# Genny_Joypad_to_Atari_Adapter.net
KiCad netlist of a schematic drawn in EAGLE
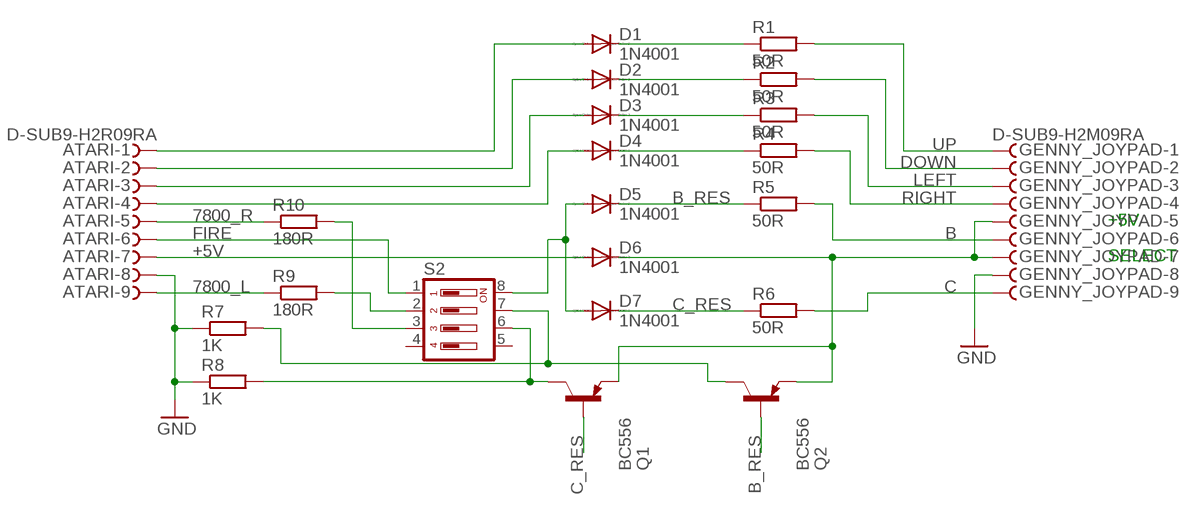
[diagram p0: schematic, sheet 1]

(export (version "E")
  (design (tool "Eeschema 10.0.6"))
  (components
    (comp (ref "ATARI")
      (value "D-SUB9-H2R09RA")
      (footprint "eagle-import:H2R09RA")
      (libsource (lib "eagle-import") (part "D-SUB9-H2R09RA"))
    )
    (comp (ref "D1")
      (value "1N4001")
      (footprint "eagle-import:DO35-7")
      (libsource (lib "eagle-import") (part "1N4148DO35-7"))
    )
    (comp (ref "D2")
      (value "1N4001")
      (footprint "eagle-import:DO35-7")
      (libsource (lib "eagle-import") (part "1N4148DO35-7"))
    )
    (comp (ref "D3")
      (value "1N4001")
      (footprint "eagle-import:DO35-7")
      (libsource (lib "eagle-import") (part "1N4148DO35-7"))
    )
    (comp (ref "D4")
      (value "1N4001")
      (footprint "eagle-import:DO35-7")
      (libsource (lib "eagle-import") (part "1N4148DO35-7"))
    )
    (comp (ref "D5")
      (value "1N4001")
      (footprint "eagle-import:DO35-7")
      (libsource (lib "eagle-import") (part "1N4148DO35-7"))
    )
    (comp (ref "D6")
      (value "1N4001")
      (footprint "eagle-import:DO35-7")
      (libsource (lib "eagle-import") (part "1N4148DO35-7"))
    )
    (comp (ref "D7")
      (value "1N4001")
      (footprint "eagle-import:DO35-7")
      (libsource (lib "eagle-import") (part "1N4148DO35-7"))
    )
    (comp (ref "GENNY_JOYPAD")
      (value "D-SUB9-H2M09RA")
      (footprint "eagle-import:H2M09RA")
      (libsource (lib "eagle-import") (part "D-SUB9-H2M09RA"))
    )
    (comp (ref "Q1")
      (value "BC556")
      (footprint "eagle-import:TO92-EBC")
      (libsource (lib "eagle-import") (part "BC556"))
    )
    (comp (ref "Q2")
      (value "BC556")
      (footprint "eagle-import:TO92-EBC")
      (libsource (lib "eagle-import") (part "BC556"))
    )
    (comp (ref "R1")
      (value "50R")
      (footprint "eagle-import:0204_7")
      (libsource (lib "eagle-import") (part "R-EU_0204/7"))
    )
    (comp (ref "R2")
      (value "50R")
      (footprint "eagle-import:0204_7")
      (libsource (lib "eagle-import") (part "R-EU_0204/7"))
    )
    (comp (ref "R3")
      (value "50R")
      (footprint "eagle-import:0204_7")
      (libsource (lib "eagle-import") (part "R-EU_0204/7"))
    )
    (comp (ref "R4")
      (value "50R")
      (footprint "eagle-import:0204_7")
      (libsource (lib "eagle-import") (part "R-EU_0204/7"))
    )
    (comp (ref "R5")
      (value "50R")
      (footprint "eagle-import:0204_7")
      (libsource (lib "eagle-import") (part "R-EU_0204/7"))
    )
    (comp (ref "R6")
      (value "50R")
      (footprint "eagle-import:0204_7")
      (libsource (lib "eagle-import") (part "R-EU_0204/7"))
    )
    (comp (ref "R7")
      (value "1K")
      (footprint "eagle-import:0204_7")
      (libsource (lib "eagle-import") (part "R-EU_0204/7"))
    )
    (comp (ref "R8")
      (value "1K")
      (footprint "eagle-import:0204_7")
      (libsource (lib "eagle-import") (part "R-EU_0204/7"))
    )
    (comp (ref "R9")
      (value "180R")
      (footprint "eagle-import:0204_7")
      (libsource (lib "eagle-import") (part "R-EU_0204/7"))
    )
    (comp (ref "R10")
      (value "180R")
      (footprint "eagle-import:0204_7")
      (libsource (lib "eagle-import") (part "R-EU_0204/7"))
    )
    (comp (ref "S2")
      (value "DIP04YL")
      (footprint "eagle-import:DIP04YL")
      (libsource (lib "eagle-import") (part "DIP04YL"))
    )
  )
  (nets
    (net (code "1") (name "/+5V") (class "Default")
      (node (ref "D6") (pin "C") (pinfunction "C_C") (pintype "passive"))
      (node (ref "GENNY_JOYPAD") (pin "5") (pinfunction "F_5") (pintype "passive"))
      (node (ref "GENNY_JOYPAD") (pin "7") (pinfunction "F_7") (pintype "passive"))
      (node (ref "Q1") (pin "E") (pinfunction "E_E") (pintype "passive"))
      (node (ref "Q2") (pin "E") (pinfunction "E_E") (pintype "passive"))
    )
    (net (code "2") (name "/7800_L") (class "Default")
      (node (ref "ATARI") (pin "9") (pinfunction "F_9") (pintype "passive"))
      (node (ref "R9") (pin "1") (pinfunction "1_1") (pintype "passive"))
    )
    (net (code "3") (name "/7800_R") (class "Default")
      (node (ref "ATARI") (pin "5") (pinfunction "F_5") (pintype "passive"))
      (node (ref "R10") (pin "1") (pinfunction "1_1") (pintype "passive"))
    )
    (net (code "4") (name "/B") (class "Default")
      (node (ref "GENNY_JOYPAD") (pin "6") (pinfunction "F_6") (pintype "passive"))
      (node (ref "R5") (pin "2") (pinfunction "2_2") (pintype "passive"))
    )
    (net (code "5") (name "/B_RES") (class "Default")
      (node (ref "D5") (pin "C") (pinfunction "C_C") (pintype "passive"))
      (node (ref "Q2") (pin "B") (pinfunction "B_B") (pintype "passive"))
      (node (ref "R5") (pin "1") (pinfunction "1_1") (pintype "passive"))
    )
    (net (code "6") (name "/C") (class "Default")
      (node (ref "GENNY_JOYPAD") (pin "9") (pinfunction "F_9") (pintype "passive"))
      (node (ref "R6") (pin "2") (pinfunction "2_2") (pintype "passive"))
    )
    (net (code "7") (name "/C_RES") (class "Default")
      (node (ref "D7") (pin "C") (pinfunction "C_C") (pintype "passive"))
      (node (ref "Q1") (pin "B") (pinfunction "B_B") (pintype "passive"))
      (node (ref "R6") (pin "1") (pinfunction "1_1") (pintype "passive"))
    )
    (net (code "8") (name "/DOWN") (class "Default")
      (node (ref "GENNY_JOYPAD") (pin "2") (pinfunction "F_2") (pintype "passive"))
      (node (ref "R2") (pin "2") (pinfunction "2_2") (pintype "passive"))
    )
    (net (code "9") (name "/FIRE") (class "Default")
      (node (ref "D5") (pin "A") (pinfunction "A_A") (pintype "passive"))
      (node (ref "D7") (pin "A") (pinfunction "A_A") (pintype "passive"))
      (node (ref "S2") (pin "8") (pinfunction "8_8") (pintype "passive"))
    )
    (net (code "10") (name "/LEFT") (class "Default")
      (node (ref "GENNY_JOYPAD") (pin "3") (pinfunction "F_3") (pintype "passive"))
      (node (ref "R3") (pin "2") (pinfunction "2_2") (pintype "passive"))
    )
    (net (code "11") (name "/RIGHT") (class "Default")
      (node (ref "GENNY_JOYPAD") (pin "4") (pinfunction "F_4") (pintype "passive"))
      (node (ref "R4") (pin "2") (pinfunction "2_2") (pintype "passive"))
    )
    (net (code "12") (name "/UP") (class "Default")
      (node (ref "GENNY_JOYPAD") (pin "1") (pinfunction "F_1") (pintype "passive"))
      (node (ref "R1") (pin "2") (pinfunction "2_2") (pintype "passive"))
    )
    (net (code "13") (name "GND") (class "Default")
      (node (ref "ATARI") (pin "8") (pinfunction "F_8") (pintype "passive"))
      (node (ref "GENNY_JOYPAD") (pin "8") (pinfunction "F_8") (pintype "passive"))
      (node (ref "R7") (pin "1") (pinfunction "1_1") (pintype "passive"))
      (node (ref "R8") (pin "1") (pinfunction "1_1") (pintype "passive"))
    )
    (net (code "14") (name "Net-(ATARIA-F)") (class "Default")
      (node (ref "ATARI") (pin "1") (pinfunction "F_1") (pintype "passive"))
      (node (ref "D1") (pin "A") (pinfunction "A_A") (pintype "passive"))
    )
    (net (code "15") (name "Net-(ATARIB-F)") (class "Default")
      (node (ref "ATARI") (pin "2") (pinfunction "F_2") (pintype "passive"))
      (node (ref "D2") (pin "A") (pinfunction "A_A") (pintype "passive"))
    )
    (net (code "16") (name "Net-(ATARIC-F)") (class "Default")
      (node (ref "ATARI") (pin "3") (pinfunction "F_3") (pintype "passive"))
      (node (ref "D3") (pin "A") (pinfunction "A_A") (pintype "passive"))
    )
    (net (code "17") (name "Net-(ATARID-F)") (class "Default")
      (node (ref "ATARI") (pin "4") (pinfunction "F_4") (pintype "passive"))
      (node (ref "D4") (pin "A") (pinfunction "A_A") (pintype "passive"))
    )
    (net (code "18") (name "Net-(ATARIF-F)") (class "Default")
      (node (ref "ATARI") (pin "6") (pinfunction "F_6") (pintype "passive"))
      (node (ref "S2") (pin "1") (pinfunction "1_1") (pintype "passive"))
    )
    (net (code "19") (name "Net-(ATARIG-F)") (class "Default")
      (node (ref "ATARI") (pin "7") (pinfunction "F_7") (pintype "passive"))
      (node (ref "D6") (pin "A") (pinfunction "A_A") (pintype "passive"))
    )
    (net (code "20") (name "Net-(D1-PadC)") (class "Default")
      (node (ref "D1") (pin "C") (pinfunction "C_C") (pintype "passive"))
      (node (ref "R1") (pin "1") (pinfunction "1_1") (pintype "passive"))
    )
    (net (code "21") (name "Net-(D2-PadC)") (class "Default")
      (node (ref "D2") (pin "C") (pinfunction "C_C") (pintype "passive"))
      (node (ref "R2") (pin "1") (pinfunction "1_1") (pintype "passive"))
    )
    (net (code "22") (name "Net-(D3-PadC)") (class "Default")
      (node (ref "D3") (pin "C") (pinfunction "C_C") (pintype "passive"))
      (node (ref "R3") (pin "1") (pinfunction "1_1") (pintype "passive"))
    )
    (net (code "23") (name "Net-(D4-PadC)") (class "Default")
      (node (ref "D4") (pin "C") (pinfunction "C_C") (pintype "passive"))
      (node (ref "R4") (pin "1") (pinfunction "1_1") (pintype "passive"))
    )
    (net (code "24") (name "Net-(Q1-PadC)") (class "Default")
      (node (ref "Q1") (pin "C") (pinfunction "C_C") (pintype "passive"))
      (node (ref "R8") (pin "2") (pinfunction "2_2") (pintype "passive"))
      (node (ref "S2") (pin "6") (pinfunction "6_6") (pintype "passive"))
    )
    (net (code "25") (name "Net-(Q2-PadC)") (class "Default")
      (node (ref "Q2") (pin "C") (pinfunction "C_C") (pintype "passive"))
      (node (ref "R7") (pin "2") (pinfunction "2_2") (pintype "passive"))
      (node (ref "S2") (pin "7") (pinfunction "7_7") (pintype "passive"))
    )
    (net (code "26") (name "Net-(R9-Pad2)") (class "Default")
      (node (ref "R9") (pin "2") (pinfunction "2_2") (pintype "passive"))
      (node (ref "S2") (pin "2") (pinfunction "2_2") (pintype "passive"))
    )
    (net (code "27") (name "Net-(R10-Pad2)") (class "Default")
      (node (ref "R10") (pin "2") (pinfunction "2_2") (pintype "passive"))
      (node (ref "S2") (pin "3") (pinfunction "3_3") (pintype "passive"))
    )
    (net (code "28") (name "unconnected-(S2-Pad4)") (class "Default")
      (node (ref "S2") (pin "4") (pinfunction "4_4") (pintype "passive"))
    )
    (net (code "29") (name "unconnected-(S2-Pad5)") (class "Default")
      (node (ref "S2") (pin "5") (pinfunction "5_5") (pintype "passive"))
    )
  )
)
